# HCLA.net
KiCad netlist of a schematic drawn in EAGLE
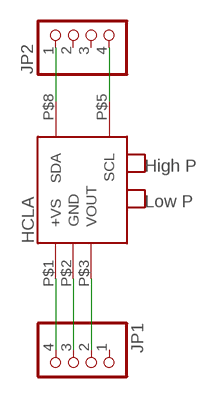
[diagram p0: schematic, sheet 1]

(export (version "E")
  (design (tool "Eeschema 10.0.6"))
  (components
    (comp (ref "JP1")
      (value "PINHD-1X4")
      (footprint "eagle-import:1X04")
      (libsource (lib "eagle-import") (part "PINHD-1X4"))
    )
    (comp (ref "JP2")
      (value "PINHD-1X4")
      (footprint "eagle-import:1X04")
      (libsource (lib "eagle-import") (part "PINHD-1X4"))
    )
    (comp (ref "U$1")
      (value "HCLA")
      (footprint "eagle-import:HCLA")
      (libsource (lib "eagle-import") (part "HCLA"))
    )
  )
  (nets
    (net (code "1") (name "Net-(U$1-+VS)") (class "Default")
      (node (ref "JP1") (pin "4") (pinfunction "4_4") (pintype "passive"))
      (node (ref "U$1") (pin "P$1") (pinfunction "+VS_P$1") (pintype "bidirectional"))
    )
    (net (code "2") (name "Net-(U$1-GND)") (class "Default")
      (node (ref "JP1") (pin "3") (pinfunction "3_3") (pintype "passive"))
      (node (ref "U$1") (pin "P$2") (pinfunction "GND_P$2") (pintype "bidirectional"))
    )
    (net (code "3") (name "Net-(U$1-SCL)") (class "Default")
      (node (ref "JP2") (pin "4") (pinfunction "4_4") (pintype "passive"))
      (node (ref "U$1") (pin "P$5") (pinfunction "SCL_P$5") (pintype "bidirectional"))
    )
    (net (code "4") (name "Net-(U$1-SDA)") (class "Default")
      (node (ref "JP2") (pin "1") (pinfunction "1_1") (pintype "passive"))
      (node (ref "U$1") (pin "P$8") (pinfunction "SDA_P$8") (pintype "bidirectional"))
    )
    (net (code "5") (name "Net-(U$1-VOUT)") (class "Default")
      (node (ref "JP1") (pin "2") (pinfunction "2_2") (pintype "passive"))
      (node (ref "U$1") (pin "P$3") (pinfunction "VOUT_P$3") (pintype "bidirectional"))
    )
    (net (code "6") (name "unconnected-(JP1-Pad1)") (class "Default")
      (node (ref "JP1") (pin "1") (pinfunction "1_1") (pintype "passive"))
    )
    (net (code "7") (name "unconnected-(JP2-Pad2)") (class "Default")
      (node (ref "JP2") (pin "2") (pinfunction "2_2") (pintype "passive"))
    )
    (net (code "8") (name "unconnected-(JP2-Pad3)") (class "Default")
      (node (ref "JP2") (pin "3") (pinfunction "3_3") (pintype "passive"))
    )
  )
)
